# e44.net
KiCad netlist of a schematic drawn in EAGLE
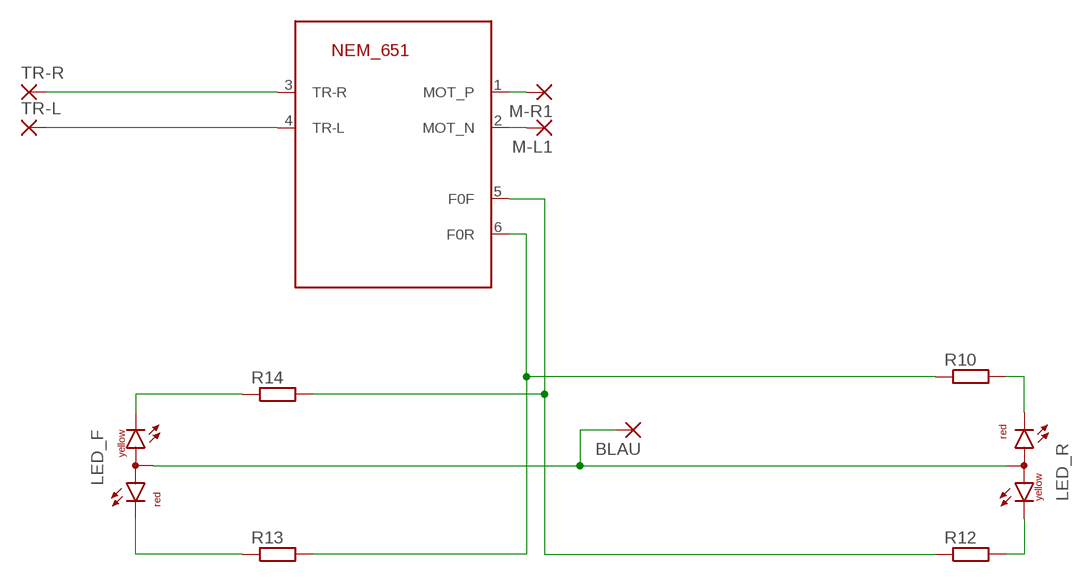
[diagram p0: schematic, sheet 1]

(export (version "E")
  (design (tool "Eeschema 10.0.6"))
  (components
    (comp (ref "651")
      (value "NEM_651-TS")
      (footprint "eagle-import:53047-06")
      (libsource (lib "eagle-import") (part "NEM_651-TS"))
    )
    (comp (ref "BLAU")
      (value "1,6/0,8")
      (footprint "eagle-import:1,6_0,8")
      (libsource (lib "eagle-import") (part "1,6/0,8"))
    )
    (comp (ref "LED_F")
      (value "DUOLED-RY-A")
      (footprint "eagle-import:DUOLED-A-5MM")
      (libsource (lib "eagle-import") (part "DUOLED-RY-A"))
    )
    (comp (ref "LED_R")
      (value "DUOLED-RY-A")
      (footprint "eagle-import:DUOLED-A-5MM")
      (libsource (lib "eagle-import") (part "DUOLED-RY-A"))
    )
    (comp (ref "M-L1")
      (value "SMD5")
      (footprint "eagle-import:SMD2,54-5,08")
      (libsource (lib "eagle-import") (part "SMD5"))
    )
    (comp (ref "M-R1")
      (value "SMD5")
      (footprint "eagle-import:SMD2,54-5,08")
      (libsource (lib "eagle-import") (part "SMD5"))
    )
    (comp (ref "R10")
      (value "R-EU_R1206")
      (footprint "eagle-import:R1206")
      (libsource (lib "eagle-import") (part "R-EU_R1206"))
    )
    (comp (ref "R12")
      (value "R-EU_R1206")
      (footprint "eagle-import:R1206")
      (libsource (lib "eagle-import") (part "R-EU_R1206"))
    )
    (comp (ref "R13")
      (value "R-EU_R1206")
      (footprint "eagle-import:R1206")
      (libsource (lib "eagle-import") (part "R-EU_R1206"))
    )
    (comp (ref "R14")
      (value "R-EU_R1206")
      (footprint "eagle-import:R1206")
      (libsource (lib "eagle-import") (part "R-EU_R1206"))
    )
    (comp (ref "TR-L")
      (value "SMD5")
      (footprint "eagle-import:SMD2,54-5,08")
      (libsource (lib "eagle-import") (part "SMD5"))
    )
    (comp (ref "TR-R")
      (value "SMD5")
      (footprint "eagle-import:SMD2,54-5,08")
      (libsource (lib "eagle-import") (part "SMD5"))
    )
  )
  (nets
    (net (code "1") (name "Net-(651-F0F)") (class "Default")
      (node (ref "651") (pin "5") (pinfunction "F0F_5") (pintype "bidirectional"))
      (node (ref "R12") (pin "1") (pinfunction "1_1") (pintype "passive"))
      (node (ref "R14") (pin "2") (pinfunction "2_2") (pintype "passive"))
    )
    (net (code "2") (name "Net-(651-F0R)") (class "Default")
      (node (ref "651") (pin "6") (pinfunction "F0R_6") (pintype "bidirectional"))
      (node (ref "R10") (pin "1") (pinfunction "1_1") (pintype "passive"))
      (node (ref "R13") (pin "2") (pinfunction "2_2") (pintype "passive"))
    )
    (net (code "3") (name "Net-(651-MOT_N)") (class "Default")
      (node (ref "651") (pin "2") (pinfunction "MOT_N_2") (pintype "bidirectional"))
      (node (ref "M-L1") (pin "1") (pinfunction "P_1") (pintype "passive"))
    )
    (net (code "4") (name "Net-(651-MOT_P)") (class "Default")
      (node (ref "651") (pin "1") (pinfunction "MOT_P_1") (pintype "bidirectional"))
      (node (ref "M-R1") (pin "1") (pinfunction "P_1") (pintype "passive"))
    )
    (net (code "5") (name "Net-(651-TR-L)") (class "Default")
      (node (ref "651") (pin "4") (pinfunction "TR-L_4") (pintype "bidirectional"))
      (node (ref "TR-L") (pin "1") (pinfunction "P_1") (pintype "passive"))
    )
    (net (code "6") (name "Net-(651-TR-R)") (class "Default")
      (node (ref "651") (pin "3") (pinfunction "TR-R_3") (pintype "bidirectional"))
      (node (ref "TR-R") (pin "1") (pinfunction "P_1") (pintype "passive"))
    )
    (net (code "7") (name "Net-(BLAU-P)") (class "Default")
      (node (ref "BLAU") (pin "1") (pinfunction "P_1") (pintype "passive"))
      (node (ref "LED_F") (pin "A") (pinfunction "A_A") (pintype "passive"))
      (node (ref "LED_R") (pin "A") (pinfunction "A_A") (pintype "passive"))
    )
    (net (code "8") (name "Net-(LED_F-CY)") (class "Default")
      (node (ref "LED_F") (pin "CX") (pinfunction "CY_CX") (pintype "passive"))
      (node (ref "R14") (pin "1") (pinfunction "1_1") (pintype "passive"))
    )
    (net (code "9") (name "Net-(LED_F-PadCR)") (class "Default")
      (node (ref "LED_F") (pin "CR") (pinfunction "CR_CR") (pintype "passive"))
      (node (ref "R13") (pin "1") (pinfunction "1_1") (pintype "passive"))
    )
    (net (code "10") (name "Net-(LED_R-CY)") (class "Default")
      (node (ref "LED_R") (pin "CX") (pinfunction "CY_CX") (pintype "passive"))
      (node (ref "R12") (pin "2") (pinfunction "2_2") (pintype "passive"))
    )
    (net (code "11") (name "Net-(LED_R-PadCR)") (class "Default")
      (node (ref "LED_R") (pin "CR") (pinfunction "CR_CR") (pintype "passive"))
      (node (ref "R10") (pin "2") (pinfunction "2_2") (pintype "passive"))
    )
  )
)
